# 464342_21-005_3_1.net
KiCad netlist of a schematic drawn in Altium Designer
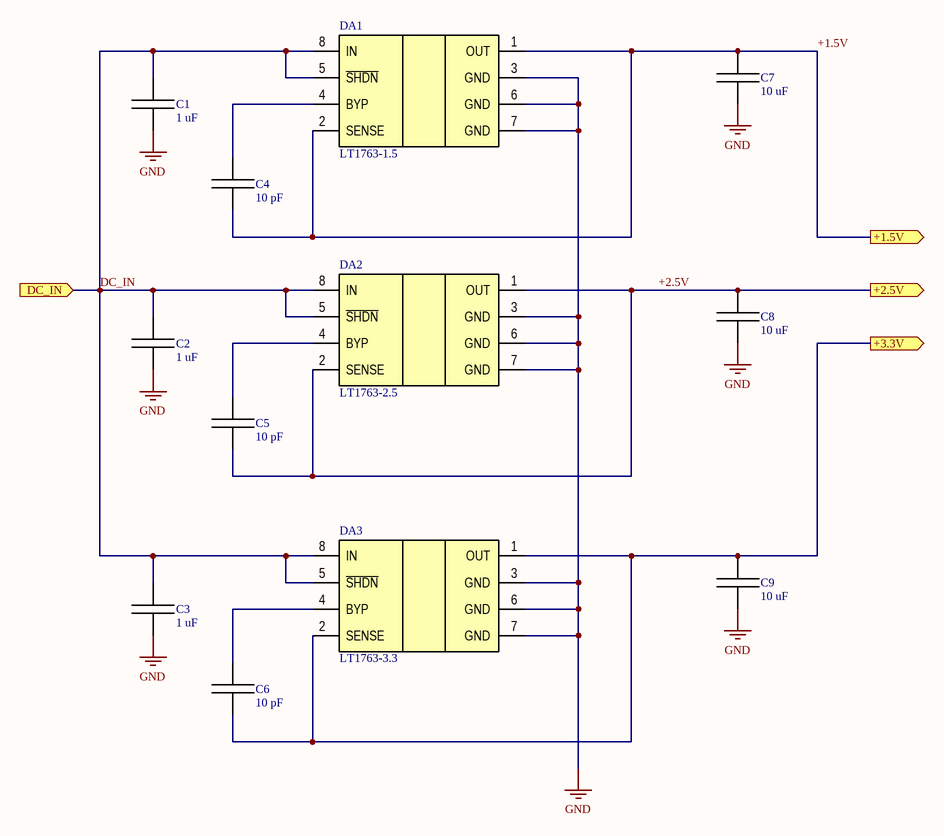
[diagram p0: МПСУ.464342.21-005Э3 Лист1.SchDoc]

(export (version "E")
  (design (tool "Eeschema 10.0.6"))
  (components
    (comp (ref "C1")
      (value "1 uF")
      (footprint "CAPC160X80X90L30N")
      (description "Capacitor, generic")
      (fields (field (name "PARTNUMBER") "X7R") (field (name "TOLERANCE") "± 10 %"))
      (libsource (lib "Discrete") (part "Capacitor"))
    )
    (comp (ref "C2")
      (value "1 uF")
      (footprint "CAPC160X80X90L30N")
      (description "Capacitor, generic")
      (fields (field (name "PARTNUMBER") "X7R") (field (name "TOLERANCE") "± 10 %"))
      (libsource (lib "Discrete") (part "Capacitor"))
    )
    (comp (ref "C3")
      (value "1 uF")
      (footprint "CAPC160X80X90L30N")
      (description "Capacitor, generic")
      (fields (field (name "PARTNUMBER") "X7R") (field (name "TOLERANCE") "± 10 %"))
      (libsource (lib "Discrete") (part "Capacitor"))
    )
    (comp (ref "C4")
      (value "10 pF")
      (footprint "CAPC160X80X90L30N")
      (description "Capacitor, generic")
      (fields (field (name "PARTNUMBER") "X7R") (field (name "TOLERANCE") "± 10 %"))
      (libsource (lib "Discrete") (part "Capacitor"))
    )
    (comp (ref "C5")
      (value "10 pF")
      (footprint "CAPC160X80X90L30N")
      (description "Capacitor, generic")
      (fields (field (name "PARTNUMBER") "X7R") (field (name "TOLERANCE") "± 10 %"))
      (libsource (lib "Discrete") (part "Capacitor"))
    )
    (comp (ref "C6")
      (value "10 pF")
      (footprint "CAPC160X80X90L30N")
      (description "Capacitor, generic")
      (fields (field (name "PARTNUMBER") "X7R") (field (name "TOLERANCE") "± 10 %"))
      (libsource (lib "Discrete") (part "Capacitor"))
    )
    (comp (ref "C7")
      (value "10 uF")
      (footprint "CAPC160X80X90L30N")
      (description "Capacitor, generic")
      (fields (field (name "PARTNUMBER") "X7R") (field (name "TOLERANCE") "± 10 %"))
      (libsource (lib "Discrete") (part "Capacitor"))
    )
    (comp (ref "C8")
      (value "10 uF")
      (footprint "CAPC160X80X90L30N")
      (description "Capacitor, generic")
      (fields (field (name "PARTNUMBER") "X7R") (field (name "TOLERANCE") "± 10 %"))
      (libsource (lib "Discrete") (part "Capacitor"))
    )
    (comp (ref "C9")
      (value "10 uF")
      (footprint "CAPC160X80X90L30N")
      (description "Capacitor, generic")
      (fields (field (name "PARTNUMBER") "X7R") (field (name "TOLERANCE") "± 10 %"))
      (libsource (lib "Discrete") (part "Capacitor"))
    )
    (comp (ref "DA1")
      (value "LT1763-1.5")
      (footprint "SOIC8P127_490X600X175L83X41N")
      (description "Micropower DC/DC Converters in SOIC8")
      (fields (field (name "MANUFACTURER") "Analog Devices"))
      (libsource (lib "PowerMangment") (part "LT1763"))
    )
    (comp (ref "DA2")
      (value "LT1763-2.5")
      (footprint "SOIC8P127_490X600X175L83X41N")
      (description "Micropower DC/DC Converters in SOIC8")
      (fields (field (name "MANUFACTURER") "Analog Devices"))
      (libsource (lib "PowerMangment") (part "LT1763"))
    )
    (comp (ref "DA3")
      (value "LT1763-3.3")
      (footprint "SOIC8P127_490X600X175L83X41N")
      (description "Micropower DC/DC Converters in SOIC8")
      (fields (field (name "MANUFACTURER") "Analog Devices"))
      (libsource (lib "PowerMangment") (part "LT1763"))
    )
  )
  (nets
    (net (code "1") (name "/+1.5V") (class "Default")
      (node (ref "C4") (pin "1") (pinfunction "1_1") (pintype "passive"))
      (node (ref "C7") (pin "2") (pinfunction "2_2") (pintype "passive"))
      (node (ref "DA1") (pin "1") (pinfunction "OUT_1") (pintype "passive"))
      (node (ref "DA1") (pin "2") (pinfunction "SENSE_2") (pintype "passive"))
    )
    (net (code "2") (name "/+2.5V") (class "Default")
      (node (ref "C5") (pin "1") (pinfunction "1_1") (pintype "passive"))
      (node (ref "C8") (pin "2") (pinfunction "2_2") (pintype "passive"))
      (node (ref "DA2") (pin "1") (pinfunction "OUT_1") (pintype "passive"))
      (node (ref "DA2") (pin "2") (pinfunction "SENSE_2") (pintype "passive"))
    )
    (net (code "3") (name "/+3.3V") (class "Default")
      (node (ref "C6") (pin "1") (pinfunction "1_1") (pintype "passive"))
      (node (ref "C9") (pin "2") (pinfunction "2_2") (pintype "passive"))
      (node (ref "DA3") (pin "1") (pinfunction "OUT_1") (pintype "passive"))
      (node (ref "DA3") (pin "2") (pinfunction "SENSE_2") (pintype "passive"))
    )
    (net (code "4") (name "/DC_IN") (class "Default")
      (node (ref "C1") (pin "2") (pinfunction "2_2") (pintype "passive"))
      (node (ref "C2") (pin "2") (pinfunction "2_2") (pintype "passive"))
      (node (ref "C3") (pin "2") (pinfunction "2_2") (pintype "passive"))
      (node (ref "DA1") (pin "5") (pinfunction "~{SHDN}_5") (pintype "passive"))
      (node (ref "DA1") (pin "8") (pinfunction "IN_8") (pintype "passive"))
      (node (ref "DA2") (pin "5") (pinfunction "~{SHDN}_5") (pintype "passive"))
      (node (ref "DA2") (pin "8") (pinfunction "IN_8") (pintype "passive"))
      (node (ref "DA3") (pin "5") (pinfunction "~{SHDN}_5") (pintype "passive"))
      (node (ref "DA3") (pin "8") (pinfunction "IN_8") (pintype "passive"))
    )
    (net (code "5") (name "GND") (class "Default")
      (node (ref "C1") (pin "1") (pinfunction "1_1") (pintype "passive"))
      (node (ref "C2") (pin "1") (pinfunction "1_1") (pintype "passive"))
      (node (ref "C3") (pin "1") (pinfunction "1_1") (pintype "passive"))
      (node (ref "C7") (pin "1") (pinfunction "1_1") (pintype "passive"))
      (node (ref "C8") (pin "1") (pinfunction "1_1") (pintype "passive"))
      (node (ref "C9") (pin "1") (pinfunction "1_1") (pintype "passive"))
      (node (ref "DA1") (pin "3") (pinfunction "GND_3") (pintype "passive"))
      (node (ref "DA1") (pin "6") (pinfunction "GND_6") (pintype "passive"))
      (node (ref "DA1") (pin "7") (pinfunction "GND_7") (pintype "passive"))
      (node (ref "DA2") (pin "3") (pinfunction "GND_3") (pintype "passive"))
      (node (ref "DA2") (pin "6") (pinfunction "GND_6") (pintype "passive"))
      (node (ref "DA2") (pin "7") (pinfunction "GND_7") (pintype "passive"))
      (node (ref "DA3") (pin "3") (pinfunction "GND_3") (pintype "passive"))
      (node (ref "DA3") (pin "6") (pinfunction "GND_6") (pintype "passive"))
      (node (ref "DA3") (pin "7") (pinfunction "GND_7") (pintype "passive"))
    )
    (net (code "6") (name "Net-(DA1-BYP)") (class "Default")
      (node (ref "C4") (pin "2") (pinfunction "2_2") (pintype "passive"))
      (node (ref "DA1") (pin "4") (pinfunction "BYP_4") (pintype "passive"))
    )
    (net (code "7") (name "Net-(DA2-BYP)") (class "Default")
      (node (ref "C5") (pin "2") (pinfunction "2_2") (pintype "passive"))
      (node (ref "DA2") (pin "4") (pinfunction "BYP_4") (pintype "passive"))
    )
    (net (code "8") (name "Net-(DA3-BYP)") (class "Default")
      (node (ref "C6") (pin "2") (pinfunction "2_2") (pintype "passive"))
      (node (ref "DA3") (pin "4") (pinfunction "BYP_4") (pintype "passive"))
    )
  )
)
